# AteGates.net
KiCad netlist of a schematic drawn in EAGLE
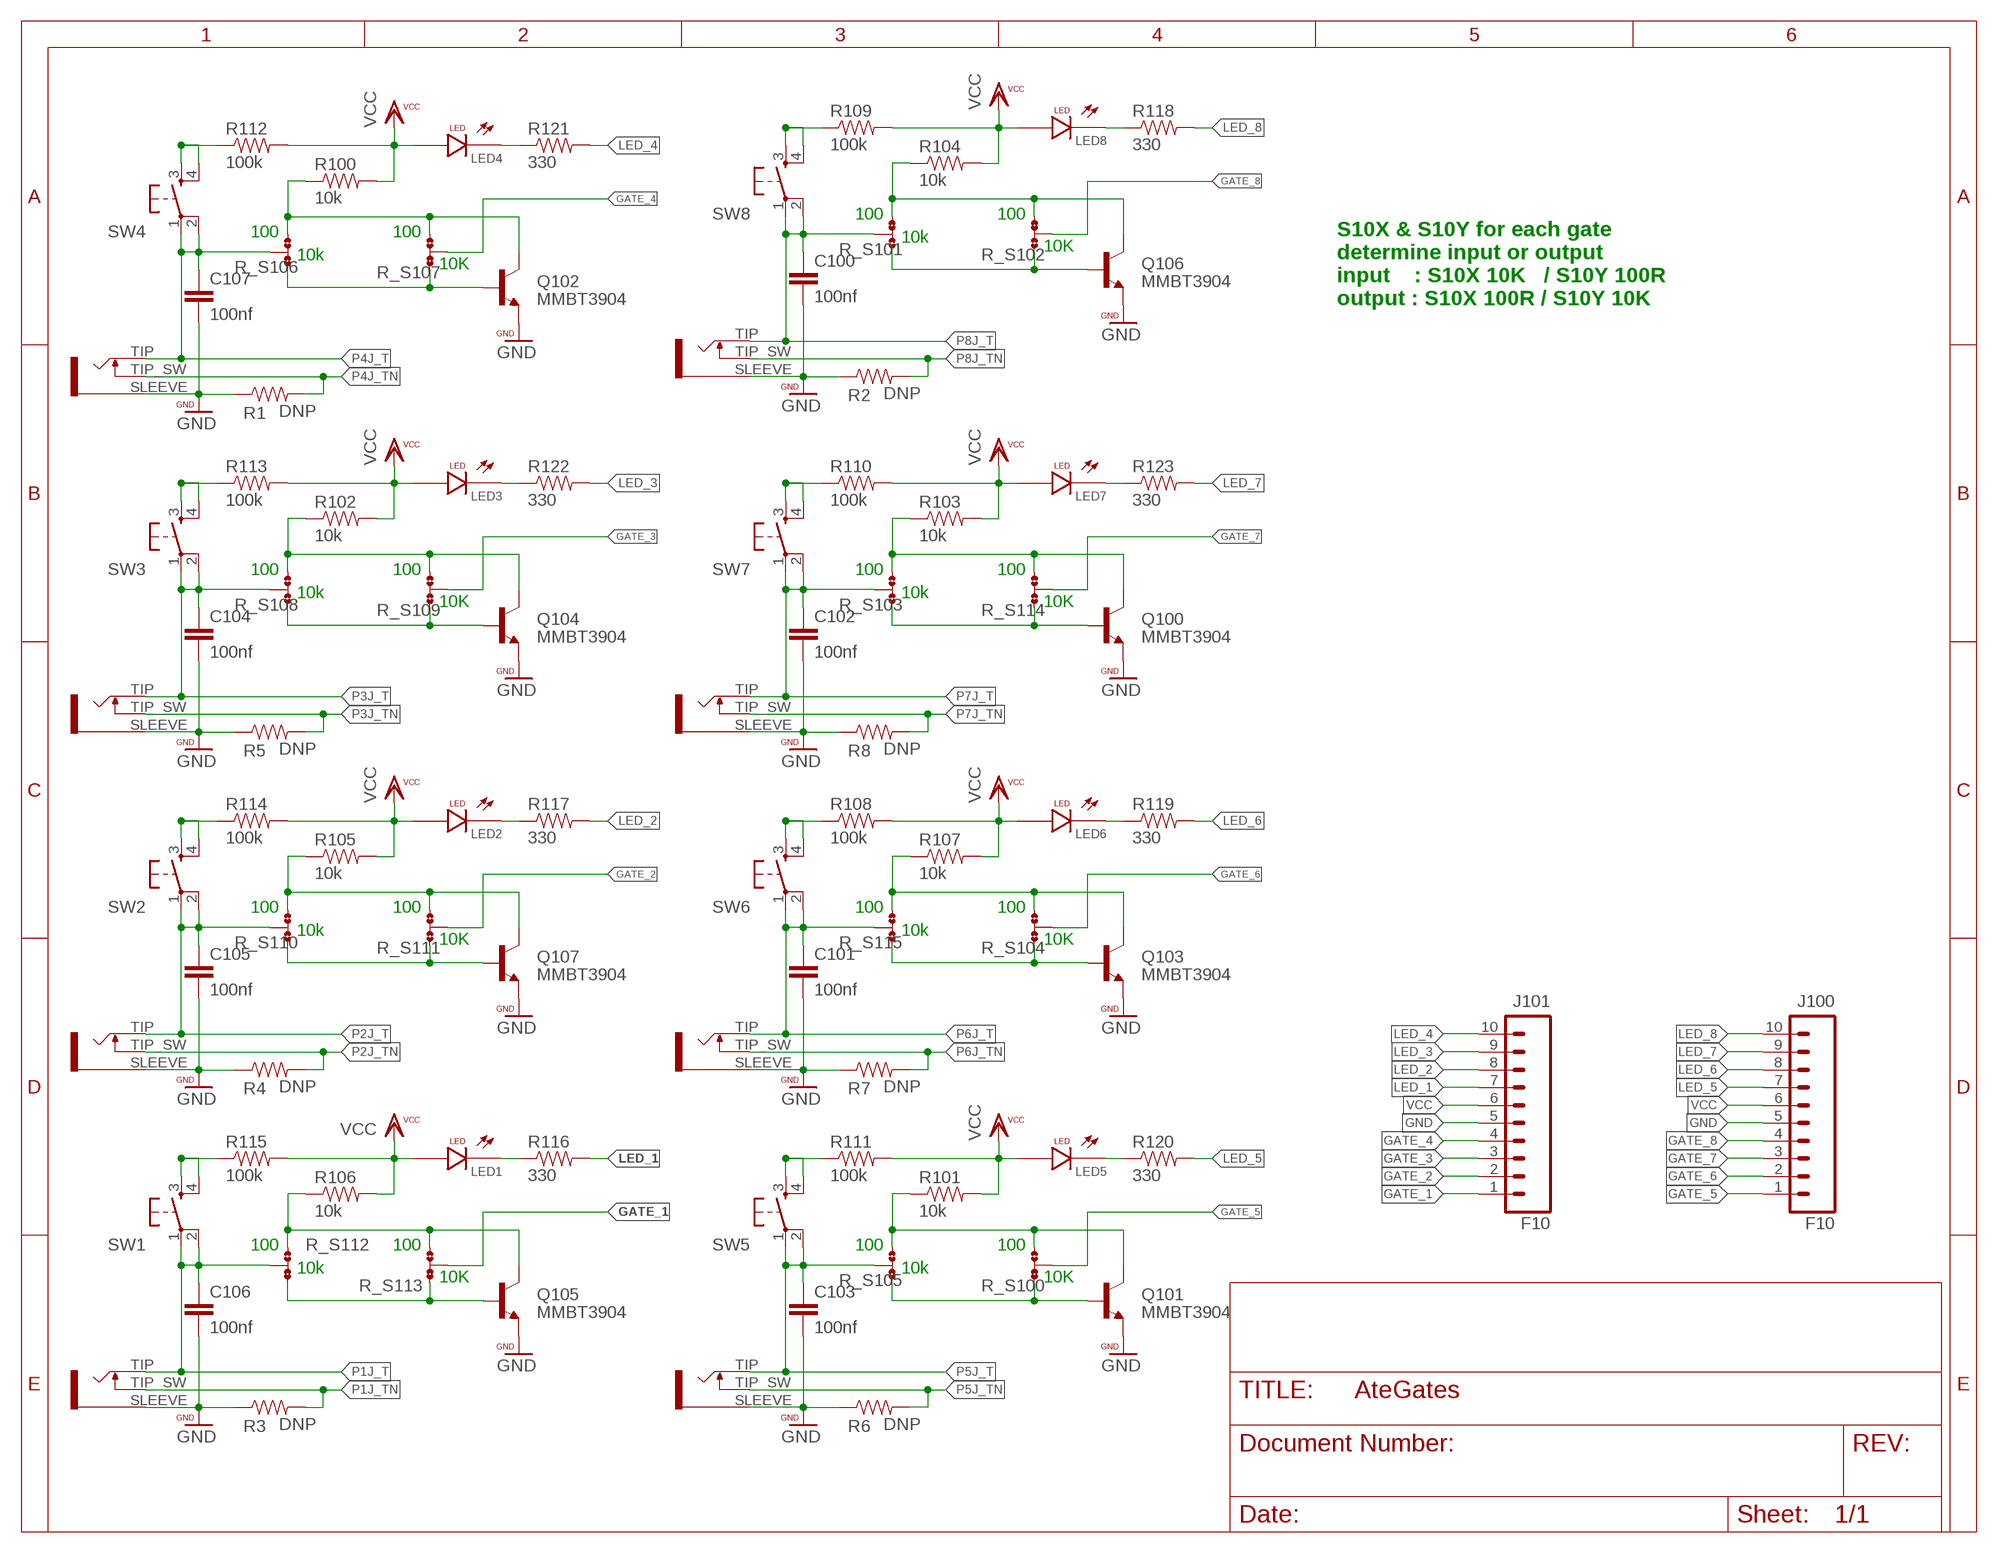
[diagram p0: schematic, sheet 1]

(export (version "E")
  (design (tool "Eeschema 10.0.6"))
  (components
    (comp (ref "C100")
      (value "100nf")
      (footprint "eagle-import:0603-CAP")
      (libsource (lib "eagle-import") (part "CAP0603-CAP"))
    )
    (comp (ref "C101")
      (value "100nf")
      (footprint "eagle-import:0603-CAP")
      (libsource (lib "eagle-import") (part "CAP0603-CAP"))
    )
    (comp (ref "C102")
      (value "100nf")
      (footprint "eagle-import:0603-CAP")
      (libsource (lib "eagle-import") (part "CAP0603-CAP"))
    )
    (comp (ref "C103")
      (value "100nf")
      (footprint "eagle-import:0603-CAP")
      (libsource (lib "eagle-import") (part "CAP0603-CAP"))
    )
    (comp (ref "C104")
      (value "100nf")
      (footprint "eagle-import:0603-CAP")
      (libsource (lib "eagle-import") (part "CAP0603-CAP"))
    )
    (comp (ref "C105")
      (value "100nf")
      (footprint "eagle-import:0603-CAP")
      (libsource (lib "eagle-import") (part "CAP0603-CAP"))
    )
    (comp (ref "C106")
      (value "100nf")
      (footprint "eagle-import:0603-CAP")
      (libsource (lib "eagle-import") (part "CAP0603-CAP"))
    )
    (comp (ref "C107")
      (value "100nf")
      (footprint "eagle-import:0603-CAP")
      (libsource (lib "eagle-import") (part "CAP0603-CAP"))
    )
    (comp (ref "J100")
      (value "F10")
      (footprint "eagle-import:1X10_OCTO")
      (libsource (lib "eagle-import") (part "M10SILK_FEMALE_PTH"))
    )
    (comp (ref "J101")
      (value "F10")
      (footprint "eagle-import:1X10_OCTO")
      (libsource (lib "eagle-import") (part "M10SILK_FEMALE_PTH"))
    )
    (comp (ref "LED1")
      (value "LED")
      (footprint "eagle-import:LED3MM")
      (libsource (lib "eagle-import") (part "LED"))
    )
    (comp (ref "LED2")
      (value "LED")
      (footprint "eagle-import:LED3MM")
      (libsource (lib "eagle-import") (part "LED"))
    )
    (comp (ref "LED3")
      (value "LED")
      (footprint "eagle-import:LED3MM")
      (libsource (lib "eagle-import") (part "LED"))
    )
    (comp (ref "LED4")
      (value "LED")
      (footprint "eagle-import:LED3MM")
      (libsource (lib "eagle-import") (part "LED"))
    )
    (comp (ref "LED5")
      (value "LED")
      (footprint "eagle-import:LED3MM")
      (libsource (lib "eagle-import") (part "LED"))
    )
    (comp (ref "LED6")
      (value "LED")
      (footprint "eagle-import:LED3MM")
      (libsource (lib "eagle-import") (part "LED"))
    )
    (comp (ref "LED7")
      (value "LED")
      (footprint "eagle-import:LED3MM")
      (libsource (lib "eagle-import") (part "LED"))
    )
    (comp (ref "LED8")
      (value "LED")
      (footprint "eagle-import:LED3MM")
      (libsource (lib "eagle-import") (part "LED"))
    )
    (comp (ref "P1J")
      (value "JACK-3_5MM-MONO-SW-WQP_PJ302-12")
      (footprint "eagle-import:WQP_PJ301M-12")
      (libsource (lib "eagle-import") (part "JACK-3_5MM-MONO-SW-WQP_PJ302-12"))
    )
    (comp (ref "P2J")
      (value "JACK-3_5MM-MONO-SW-WQP_PJ302-12")
      (footprint "eagle-import:WQP_PJ301M-12")
      (libsource (lib "eagle-import") (part "JACK-3_5MM-MONO-SW-WQP_PJ302-12"))
    )
    (comp (ref "P3J")
      (value "JACK-3_5MM-MONO-SW-WQP_PJ302-12")
      (footprint "eagle-import:WQP_PJ301M-12")
      (libsource (lib "eagle-import") (part "JACK-3_5MM-MONO-SW-WQP_PJ302-12"))
    )
    (comp (ref "P4J")
      (value "JACK-3_5MM-MONO-SW-WQP_PJ302-12")
      (footprint "eagle-import:WQP_PJ301M-12")
      (libsource (lib "eagle-import") (part "JACK-3_5MM-MONO-SW-WQP_PJ302-12"))
    )
    (comp (ref "P5J")
      (value "JACK-3_5MM-MONO-SW-WQP_PJ302-12")
      (footprint "eagle-import:WQP_PJ301M-12")
      (libsource (lib "eagle-import") (part "JACK-3_5MM-MONO-SW-WQP_PJ302-12"))
    )
    (comp (ref "P6J")
      (value "JACK-3_5MM-MONO-SW-WQP_PJ302-12")
      (footprint "eagle-import:WQP_PJ301M-12")
      (libsource (lib "eagle-import") (part "JACK-3_5MM-MONO-SW-WQP_PJ302-12"))
    )
    (comp (ref "P7J")
      (value "JACK-3_5MM-MONO-SW-WQP_PJ302-12")
      (footprint "eagle-import:WQP_PJ301M-12")
      (libsource (lib "eagle-import") (part "JACK-3_5MM-MONO-SW-WQP_PJ302-12"))
    )
    (comp (ref "P8J")
      (value "JACK-3_5MM-MONO-SW-WQP_PJ302-12")
      (footprint "eagle-import:WQP_PJ301M-12")
      (libsource (lib "eagle-import") (part "JACK-3_5MM-MONO-SW-WQP_PJ302-12"))
    )
    (comp (ref "Q100")
      (value "MMBT3904")
      (footprint "eagle-import:SOT23-BEC")
      (libsource (lib "eagle-import") (part "-NPN-SOT23-BECMMBT3904LT1"))
    )
    (comp (ref "Q101")
      (value "MMBT3904")
      (footprint "eagle-import:SOT23-BEC")
      (libsource (lib "eagle-import") (part "-NPN-SOT23-BECMMBT3904LT1"))
    )
    (comp (ref "Q102")
      (value "MMBT3904")
      (footprint "eagle-import:SOT23-BEC")
      (libsource (lib "eagle-import") (part "-NPN-SOT23-BECMMBT3904LT1"))
    )
    (comp (ref "Q103")
      (value "MMBT3904")
      (footprint "eagle-import:SOT23-BEC")
      (libsource (lib "eagle-import") (part "-NPN-SOT23-BECMMBT3904LT1"))
    )
    (comp (ref "Q104")
      (value "MMBT3904")
      (footprint "eagle-import:SOT23-BEC")
      (libsource (lib "eagle-import") (part "-NPN-SOT23-BECMMBT3904LT1"))
    )
    (comp (ref "Q105")
      (value "MMBT3904")
      (footprint "eagle-import:SOT23-BEC")
      (libsource (lib "eagle-import") (part "-NPN-SOT23-BECMMBT3904LT1"))
    )
    (comp (ref "Q106")
      (value "MMBT3904")
      (footprint "eagle-import:SOT23-BEC")
      (libsource (lib "eagle-import") (part "-NPN-SOT23-BECMMBT3904LT1"))
    )
    (comp (ref "Q107")
      (value "MMBT3904")
      (footprint "eagle-import:SOT23-BEC")
      (libsource (lib "eagle-import") (part "-NPN-SOT23-BECMMBT3904LT1"))
    )
    (comp (ref "R1")
      (value "DNP")
      (footprint "eagle-import:0603-RES")
      (libsource (lib "eagle-import") (part "RESISTOR0603-RES"))
    )
    (comp (ref "R2")
      (value "DNP")
      (footprint "eagle-import:0603-RES")
      (libsource (lib "eagle-import") (part "RESISTOR0603-RES"))
    )
    (comp (ref "R3")
      (value "DNP")
      (footprint "eagle-import:0603-RES")
      (libsource (lib "eagle-import") (part "RESISTOR0603-RES"))
    )
    (comp (ref "R4")
      (value "DNP")
      (footprint "eagle-import:0603-RES")
      (libsource (lib "eagle-import") (part "RESISTOR0603-RES"))
    )
    (comp (ref "R5")
      (value "DNP")
      (footprint "eagle-import:0603-RES")
      (libsource (lib "eagle-import") (part "RESISTOR0603-RES"))
    )
    (comp (ref "R6")
      (value "DNP")
      (footprint "eagle-import:0603-RES")
      (libsource (lib "eagle-import") (part "RESISTOR0603-RES"))
    )
    (comp (ref "R7")
      (value "DNP")
      (footprint "eagle-import:0603-RES")
      (libsource (lib "eagle-import") (part "RESISTOR0603-RES"))
    )
    (comp (ref "R8")
      (value "DNP")
      (footprint "eagle-import:0603-RES")
      (libsource (lib "eagle-import") (part "RESISTOR0603-RES"))
    )
    (comp (ref "R100")
      (value "10k")
      (footprint "eagle-import:0603-RES")
      (libsource (lib "eagle-import") (part "RESISTOR0603-RES"))
    )
    (comp (ref "R101")
      (value "10k")
      (footprint "eagle-import:0603-RES")
      (libsource (lib "eagle-import") (part "RESISTOR0603-RES"))
    )
    (comp (ref "R102")
      (value "10k")
      (footprint "eagle-import:0603-RES")
      (libsource (lib "eagle-import") (part "RESISTOR0603-RES"))
    )
    (comp (ref "R103")
      (value "10k")
      (footprint "eagle-import:0603-RES")
      (libsource (lib "eagle-import") (part "RESISTOR0603-RES"))
    )
    (comp (ref "R104")
      (value "10k")
      (footprint "eagle-import:0603-RES")
      (libsource (lib "eagle-import") (part "RESISTOR0603-RES"))
    )
    (comp (ref "R105")
      (value "10k")
      (footprint "eagle-import:0603-RES")
      (libsource (lib "eagle-import") (part "RESISTOR0603-RES"))
    )
    (comp (ref "R106")
      (value "10k")
      (footprint "eagle-import:0603-RES")
      (libsource (lib "eagle-import") (part "RESISTOR0603-RES"))
    )
    (comp (ref "R107")
      (value "10k")
      (footprint "eagle-import:0603-RES")
      (libsource (lib "eagle-import") (part "RESISTOR0603-RES"))
    )
    (comp (ref "R108")
      (value "100k")
      (footprint "eagle-import:0603-RES")
      (libsource (lib "eagle-import") (part "RESISTOR0603-RES"))
    )
    (comp (ref "R109")
      (value "100k")
      (footprint "eagle-import:0603-RES")
      (libsource (lib "eagle-import") (part "RESISTOR0603-RES"))
    )
    (comp (ref "R110")
      (value "100k")
      (footprint "eagle-import:0603-RES")
      (libsource (lib "eagle-import") (part "RESISTOR0603-RES"))
    )
    (comp (ref "R111")
      (value "100k")
      (footprint "eagle-import:0603-RES")
      (libsource (lib "eagle-import") (part "RESISTOR0603-RES"))
    )
    (comp (ref "R112")
      (value "100k")
      (footprint "eagle-import:0603-RES")
      (libsource (lib "eagle-import") (part "RESISTOR0603-RES"))
    )
    (comp (ref "R113")
      (value "100k")
      (footprint "eagle-import:0603-RES")
      (libsource (lib "eagle-import") (part "RESISTOR0603-RES"))
    )
    (comp (ref "R114")
      (value "100k")
      (footprint "eagle-import:0603-RES")
      (libsource (lib "eagle-import") (part "RESISTOR0603-RES"))
    )
    (comp (ref "R115")
      (value "100k")
      (footprint "eagle-import:0603-RES")
      (libsource (lib "eagle-import") (part "RESISTOR0603-RES"))
    )
    (comp (ref "R116")
      (value "330")
      (footprint "eagle-import:0603-RES")
      (libsource (lib "eagle-import") (part "RESISTOR0603-RES"))
    )
    (comp (ref "R117")
      (value "330")
      (footprint "eagle-import:0603-RES")
      (libsource (lib "eagle-import") (part "RESISTOR0603-RES"))
    )
    (comp (ref "R118")
      (value "330")
      (footprint "eagle-import:0603-RES")
      (libsource (lib "eagle-import") (part "RESISTOR0603-RES"))
    )
    (comp (ref "R119")
      (value "330")
      (footprint "eagle-import:0603-RES")
      (libsource (lib "eagle-import") (part "RESISTOR0603-RES"))
    )
    (comp (ref "R120")
      (value "330")
      (footprint "eagle-import:0603-RES")
      (libsource (lib "eagle-import") (part "RESISTOR0603-RES"))
    )
    (comp (ref "R121")
      (value "330")
      (footprint "eagle-import:0603-RES")
      (libsource (lib "eagle-import") (part "RESISTOR0603-RES"))
    )
    (comp (ref "R122")
      (value "330")
      (footprint "eagle-import:0603-RES")
      (libsource (lib "eagle-import") (part "RESISTOR0603-RES"))
    )
    (comp (ref "R123")
      (value "330")
      (footprint "eagle-import:0603-RES")
      (libsource (lib "eagle-import") (part "RESISTOR0603-RES"))
    )
    (comp (ref "R_S100")
      (value "JMP-3-NO-0603")
      (footprint "eagle-import:JMP-3-NO-0603")
      (libsource (lib "eagle-import") (part "JMP-3-NO-0603"))
    )
    (comp (ref "R_S101")
      (value "100")
      (footprint "eagle-import:JMP-3-NO-0603")
      (libsource (lib "eagle-import") (part "JMP-3-NO-0603"))
    )
    (comp (ref "R_S102")
      (value "JMP-3-NO-0603")
      (footprint "eagle-import:JMP-3-NO-0603")
      (libsource (lib "eagle-import") (part "JMP-3-NO-0603"))
    )
    (comp (ref "R_S103")
      (value "100")
      (footprint "eagle-import:JMP-3-NO-0603")
      (libsource (lib "eagle-import") (part "JMP-3-NO-0603"))
    )
    (comp (ref "R_S104")
      (value "JMP-3-NO-0603")
      (footprint "eagle-import:JMP-3-NO-0603")
      (libsource (lib "eagle-import") (part "JMP-3-NO-0603"))
    )
    (comp (ref "R_S105")
      (value "100")
      (footprint "eagle-import:JMP-3-NO-0603")
      (libsource (lib "eagle-import") (part "JMP-3-NO-0603"))
    )
    (comp (ref "R_S106")
      (value "100")
      (footprint "eagle-import:JMP-3-NO-0603")
      (libsource (lib "eagle-import") (part "JMP-3-NO-0603"))
    )
    (comp (ref "R_S107")
      (value "JMP-3-NO-0603")
      (footprint "eagle-import:JMP-3-NO-0603")
      (libsource (lib "eagle-import") (part "JMP-3-NO-0603"))
    )
    (comp (ref "R_S108")
      (value "100")
      (footprint "eagle-import:JMP-3-NO-0603")
      (libsource (lib "eagle-import") (part "JMP-3-NO-0603"))
    )
    (comp (ref "R_S109")
      (value "JMP-3-NO-0603")
      (footprint "eagle-import:JMP-3-NO-0603")
      (libsource (lib "eagle-import") (part "JMP-3-NO-0603"))
    )
    (comp (ref "R_S110")
      (value "100")
      (footprint "eagle-import:JMP-3-NO-0603")
      (libsource (lib "eagle-import") (part "JMP-3-NO-0603"))
    )
    (comp (ref "R_S111")
      (value "JMP-3-NO-0603")
      (footprint "eagle-import:JMP-3-NO-0603")
      (libsource (lib "eagle-import") (part "JMP-3-NO-0603"))
    )
    (comp (ref "R_S112")
      (value "100")
      (footprint "eagle-import:JMP-3-NO-0603")
      (libsource (lib "eagle-import") (part "JMP-3-NO-0603"))
    )
    (comp (ref "R_S113")
      (value "JMP-3-NO-0603")
      (footprint "eagle-import:JMP-3-NO-0603")
      (libsource (lib "eagle-import") (part "JMP-3-NO-0603"))
    )
    (comp (ref "R_S114")
      (value "JMP-3-NO-0603")
      (footprint "eagle-import:JMP-3-NO-0603")
      (libsource (lib "eagle-import") (part "JMP-3-NO-0603"))
    )
    (comp (ref "R_S115")
      (value "100")
      (footprint "eagle-import:JMP-3-NO-0603")
      (libsource (lib "eagle-import") (part "JMP-3-NO-0603"))
    )
    (comp (ref "SW1")
      (value "TAC_SWITCHPTH")
      (footprint "eagle-import:TACTILE-PTH")
      (libsource (lib "eagle-import") (part "TAC_SWITCHPTH"))
    )
    (comp (ref "SW2")
      (value "TAC_SWITCHPTH")
      (footprint "eagle-import:TACTILE-PTH")
      (libsource (lib "eagle-import") (part "TAC_SWITCHPTH"))
    )
    (comp (ref "SW3")
      (value "TAC_SWITCHPTH")
      (footprint "eagle-import:TACTILE-PTH")
      (libsource (lib "eagle-import") (part "TAC_SWITCHPTH"))
    )
    (comp (ref "SW4")
      (value "TAC_SWITCHPTH")
      (footprint "eagle-import:TACTILE-PTH")
      (libsource (lib "eagle-import") (part "TAC_SWITCHPTH"))
    )
    (comp (ref "SW5")
      (value "TAC_SWITCHPTH")
      (footprint "eagle-import:TACTILE-PTH")
      (libsource (lib "eagle-import") (part "TAC_SWITCHPTH"))
    )
    (comp (ref "SW6")
      (value "TAC_SWITCHPTH")
      (footprint "eagle-import:TACTILE-PTH")
      (libsource (lib "eagle-import") (part "TAC_SWITCHPTH"))
    )
    (comp (ref "SW7")
      (value "TAC_SWITCHPTH")
      (footprint "eagle-import:TACTILE-PTH")
      (libsource (lib "eagle-import") (part "TAC_SWITCHPTH"))
    )
    (comp (ref "SW8")
      (value "TAC_SWITCHPTH")
      (footprint "eagle-import:TACTILE-PTH")
      (libsource (lib "eagle-import") (part "TAC_SWITCHPTH"))
    )
  )
  (nets
    (net (code "1") (name "GATE_1") (class "Default")
      (node (ref "J101") (pin "1") (pinfunction "1_1") (pintype "passive"))
      (node (ref "R_S113") (pin "2") (pinfunction "2_2") (pintype "passive"))
    )
    (net (code "2") (name "GATE_2") (class "Default")
      (node (ref "J101") (pin "2") (pinfunction "2_2") (pintype "passive"))
      (node (ref "R_S111") (pin "2") (pinfunction "2_2") (pintype "passive"))
    )
    (net (code "3") (name "GATE_3") (class "Default")
      (node (ref "J101") (pin "3") (pinfunction "3_3") (pintype "passive"))
      (node (ref "R_S109") (pin "2") (pinfunction "2_2") (pintype "passive"))
    )
    (net (code "4") (name "GATE_4") (class "Default")
      (node (ref "J101") (pin "4") (pinfunction "4_4") (pintype "passive"))
      (node (ref "R_S107") (pin "2") (pinfunction "2_2") (pintype "passive"))
    )
    (net (code "5") (name "GATE_5") (class "Default")
      (node (ref "J100") (pin "1") (pinfunction "1_1") (pintype "passive"))
      (node (ref "R_S100") (pin "2") (pinfunction "2_2") (pintype "passive"))
    )
    (net (code "6") (name "GATE_6") (class "Default")
      (node (ref "J100") (pin "2") (pinfunction "2_2") (pintype "passive"))
      (node (ref "R_S104") (pin "2") (pinfunction "2_2") (pintype "passive"))
    )
    (net (code "7") (name "GATE_7") (class "Default")
      (node (ref "J100") (pin "3") (pinfunction "3_3") (pintype "passive"))
      (node (ref "R_S114") (pin "2") (pinfunction "2_2") (pintype "passive"))
    )
    (net (code "8") (name "GATE_8") (class "Default")
      (node (ref "J100") (pin "4") (pinfunction "4_4") (pintype "passive"))
      (node (ref "R_S102") (pin "2") (pinfunction "2_2") (pintype "passive"))
    )
    (net (code "9") (name "GND") (class "Default")
      (node (ref "C100") (pin "2") (pinfunction "2_2") (pintype "passive"))
      (node (ref "C101") (pin "2") (pinfunction "2_2") (pintype "passive"))
      (node (ref "C102") (pin "2") (pinfunction "2_2") (pintype "passive"))
      (node (ref "C103") (pin "2") (pinfunction "2_2") (pintype "passive"))
      (node (ref "C104") (pin "2") (pinfunction "2_2") (pintype "passive"))
      (node (ref "C105") (pin "2") (pinfunction "2_2") (pintype "passive"))
      (node (ref "C106") (pin "2") (pinfunction "2_2") (pintype "passive"))
      (node (ref "C107") (pin "2") (pinfunction "2_2") (pintype "passive"))
      (node (ref "J100") (pin "5") (pinfunction "5_5") (pintype "passive"))
      (node (ref "J101") (pin "5") (pinfunction "5_5") (pintype "passive"))
      (node (ref "P1J") (pin "SLEEVE") (pinfunction "SLEEVE_SLEEVE") (pintype "passive"))
      (node (ref "P2J") (pin "SLEEVE") (pinfunction "SLEEVE_SLEEVE") (pintype "passive"))
      (node (ref "P3J") (pin "SLEEVE") (pinfunction "SLEEVE_SLEEVE") (pintype "passive"))
      (node (ref "P4J") (pin "SLEEVE") (pinfunction "SLEEVE_SLEEVE") (pintype "passive"))
      (node (ref "P5J") (pin "SLEEVE") (pinfunction "SLEEVE_SLEEVE") (pintype "passive"))
      (node (ref "P6J") (pin "SLEEVE") (pinfunction "SLEEVE_SLEEVE") (pintype "passive"))
      (node (ref "P7J") (pin "SLEEVE") (pinfunction "SLEEVE_SLEEVE") (pintype "passive"))
      (node (ref "P8J") (pin "SLEEVE") (pinfunction "SLEEVE_SLEEVE") (pintype "passive"))
      (node (ref "Q100") (pin "E") (pinfunction "E_E") (pintype "passive"))
      (node (ref "Q101") (pin "E") (pinfunction "E_E") (pintype "passive"))
      (node (ref "Q102") (pin "E") (pinfunction "E_E") (pintype "passive"))
      (node (ref "Q103") (pin "E") (pinfunction "E_E") (pintype "passive"))
      (node (ref "Q104") (pin "E") (pinfunction "E_E") (pintype "passive"))
      (node (ref "Q105") (pin "E") (pinfunction "E_E") (pintype "passive"))
      (node (ref "Q106") (pin "E") (pinfunction "E_E") (pintype "passive"))
      (node (ref "Q107") (pin "E") (pinfunction "E_E") (pintype "passive"))
      (node (ref "R1") (pin "1") (pinfunction "1_1") (pintype "passive"))
      (node (ref "R2") (pin "1") (pinfunction "1_1") (pintype "passive"))
      (node (ref "R3") (pin "1") (pinfunction "1_1") (pintype "passive"))
      (node (ref "R4") (pin "1") (pinfunction "1_1") (pintype "passive"))
      (node (ref "R5") (pin "1") (pinfunction "1_1") (pintype "passive"))
      (node (ref "R6") (pin "1") (pinfunction "1_1") (pintype "passive"))
      (node (ref "R7") (pin "1") (pinfunction "1_1") (pintype "passive"))
      (node (ref "R8") (pin "1") (pinfunction "1_1") (pintype "passive"))
    )
    (net (code "10") (name "LED_1") (class "Default")
      (node (ref "J101") (pin "7") (pinfunction "7_7") (pintype "passive"))
      (node (ref "R116") (pin "2") (pinfunction "2_2") (pintype "passive"))
    )
    (net (code "11") (name "LED_2") (class "Default")
      (node (ref "J101") (pin "8") (pinfunction "8_8") (pintype "passive"))
      (node (ref "R117") (pin "2") (pinfunction "2_2") (pintype "passive"))
    )
    (net (code "12") (name "LED_3") (class "Default")
      (node (ref "J101") (pin "9") (pinfunction "9_9") (pintype "passive"))
      (node (ref "R122") (pin "2") (pinfunction "2_2") (pintype "passive"))
    )
    (net (code "13") (name "LED_4") (class "Default")
      (node (ref "J101") (pin "10") (pinfunction "10_10") (pintype "passive"))
      (node (ref "R121") (pin "2") (pinfunction "2_2") (pintype "passive"))
    )
    (net (code "14") (name "LED_5") (class "Default")
      (node (ref "J100") (pin "7") (pinfunction "7_7") (pintype "passive"))
      (node (ref "R120") (pin "2") (pinfunction "2_2") (pintype "passive"))
    )
    (net (code "15") (name "LED_6") (class "Default")
      (node (ref "J100") (pin "8") (pinfunction "8_8") (pintype "passive"))
      (node (ref "R119") (pin "2") (pinfunction "2_2") (pintype "passive"))
    )
    (net (code "16") (name "LED_7") (class "Default")
      (node (ref "J100") (pin "9") (pinfunction "9_9") (pintype "passive"))
      (node (ref "R123") (pin "2") (pinfunction "2_2") (pintype "passive"))
    )
    (net (code "17") (name "LED_8") (class "Default")
      (node (ref "J100") (pin "10") (pinfunction "10_10") (pintype "passive"))
      (node (ref "R118") (pin "2") (pinfunction "2_2") (pintype "passive"))
    )
    (net (code "18") (name "Net-(LED1-CATHODE)") (class "Default")
      (node (ref "LED1") (pin "K") (pinfunction "CATHODE_K") (pintype "bidirectional"))
      (node (ref "R116") (pin "1") (pinfunction "1_1") (pintype "passive"))
    )
    (net (code "19") (name "Net-(LED2-CATHODE)") (class "Default")
      (node (ref "LED2") (pin "K") (pinfunction "CATHODE_K") (pintype "bidirectional"))
      (node (ref "R117") (pin "1") (pinfunction "1_1") (pintype "passive"))
    )
    (net (code "20") (name "Net-(LED3-CATHODE)") (class "Default")
      (node (ref "LED3") (pin "K") (pinfunction "CATHODE_K") (pintype "bidirectional"))
      (node (ref "R122") (pin "1") (pinfunction "1_1") (pintype "passive"))
    )
    (net (code "21") (name "Net-(LED4-CATHODE)") (class "Default")
      (node (ref "LED4") (pin "K") (pinfunction "CATHODE_K") (pintype "bidirectional"))
      (node (ref "R121") (pin "1") (pinfunction "1_1") (pintype "passive"))
    )
    (net (code "22") (name "Net-(LED5-CATHODE)") (class "Default")
      (node (ref "LED5") (pin "K") (pinfunction "CATHODE_K") (pintype "bidirectional"))
      (node (ref "R120") (pin "1") (pinfunction "1_1") (pintype "passive"))
    )
    (net (code "23") (name "Net-(LED6-CATHODE)") (class "Default")
      (node (ref "LED6") (pin "K") (pinfunction "CATHODE_K") (pintype "bidirectional"))
      (node (ref "R119") (pin "1") (pinfunction "1_1") (pintype "passive"))
    )
    (net (code "24") (name "Net-(LED7-CATHODE)") (class "Default")
      (node (ref "LED7") (pin "K") (pinfunction "CATHODE_K") (pintype "bidirectional"))
      (node (ref "R123") (pin "1") (pinfunction "1_1") (pintype "passive"))
    )
    (net (code "25") (name "Net-(LED8-CATHODE)") (class "Default")
      (node (ref "LED8") (pin "K") (pinfunction "CATHODE_K") (pintype "bidirectional"))
      (node (ref "R118") (pin "1") (pinfunction "1_1") (pintype "passive"))
    )
    (net (code "26") (name "Net-(Q100-PadB)") (class "Default")
      (node (ref "Q100") (pin "B") (pinfunction "B_B") (pintype "passive"))
      (node (ref "R_S103") (pin "3") (pinfunction "3_3") (pintype "passive"))
      (node (ref "R_S114") (pin "3") (pinfunction "3_3") (pintype "passive"))
    )
    (net (code "27") (name "Net-(Q100-PadC)") (class "Default")
      (node (ref "Q100") (pin "C") (pinfunction "C_C") (pintype "passive"))
      (node (ref "R103") (pin "1") (pinfunction "1_1") (pintype "passive"))
      (node (ref "R_S103") (pin "1") (pinfunction "1_1") (pintype "passive"))
      (node (ref "R_S114") (pin "1") (pinfunction "1_1") (pintype "passive"))
    )
    (net (code "28") (name "Net-(Q101-PadB)") (class "Default")
      (node (ref "Q101") (pin "B") (pinfunction "B_B") (pintype "passive"))
      (node (ref "R_S100") (pin "3") (pinfunction "3_3") (pintype "passive"))
      (node (ref "R_S105") (pin "3") (pinfunction "3_3") (pintype "passive"))
    )
    (net (code "29") (name "Net-(Q101-PadC)") (class "Default")
      (node (ref "Q101") (pin "C") (pinfunction "C_C") (pintype "passive"))
      (node (ref "R101") (pin "1") (pinfunction "1_1") (pintype "passive"))
      (node (ref "R_S100") (pin "1") (pinfunction "1_1") (pintype "passive"))
      (node (ref "R_S105") (pin "1") (pinfunction "1_1") (pintype "passive"))
    )
    (net (code "30") (name "Net-(Q102-PadB)") (class "Default")
      (node (ref "Q102") (pin "B") (pinfunction "B_B") (pintype "passive"))
      (node (ref "R_S106") (pin "3") (pinfunction "3_3") (pintype "passive"))
      (node (ref "R_S107") (pin "3") (pinfunction "3_3") (pintype "passive"))
    )
    (net (code "31") (name "Net-(Q102-PadC)") (class "Default")
      (node (ref "Q102") (pin "C") (pinfunction "C_C") (pintype "passive"))
      (node (ref "R100") (pin "1") (pinfunction "1_1") (pintype "passive"))
      (node (ref "R_S106") (pin "1") (pinfunction "1_1") (pintype "passive"))
      (node (ref "R_S107") (pin "1") (pinfunction "1_1") (pintype "passive"))
    )
    (net (code "32") (name "Net-(Q103-PadB)") (class "Default")
      (node (ref "Q103") (pin "B") (pinfunction "B_B") (pintype "passive"))
      (node (ref "R_S104") (pin "3") (pinfunction "3_3") (pintype "passive"))
      (node (ref "R_S115") (pin "3") (pinfunction "3_3") (pintype "passive"))
    )
    (net (code "33") (name "Net-(Q103-PadC)") (class "Default")
      (node (ref "Q103") (pin "C") (pinfunction "C_C") (pintype "passive"))
      (node (ref "R107") (pin "1") (pinfunction "1_1") (pintype "passive"))
      (node (ref "R_S104") (pin "1") (pinfunction "1_1") (pintype "passive"))
      (node (ref "R_S115") (pin "1") (pinfunction "1_1") (pintype "passive"))
    )
    (net (code "34") (name "Net-(Q104-PadB)") (class "Default")
      (node (ref "Q104") (pin "B") (pinfunction "B_B") (pintype "passive"))
      (node (ref "R_S108") (pin "3") (pinfunction "3_3") (pintype "passive"))
      (node (ref "R_S109") (pin "3") (pinfunction "3_3") (pintype "passive"))
    )
    (net (code "35") (name "Net-(Q104-PadC)") (class "Default")
      (node (ref "Q104") (pin "C") (pinfunction "C_C") (pintype "passive"))
      (node (ref "R102") (pin "1") (pinfunction "1_1") (pintype "passive"))
      (node (ref "R_S108") (pin "1") (pinfunction "1_1") (pintype "passive"))
      (node (ref "R_S109") (pin "1") (pinfunction "1_1") (pintype "passive"))
    )
    (net (code "36") (name "Net-(Q105-PadB)") (class "Default")
      (node (ref "Q105") (pin "B") (pinfunction "B_B") (pintype "passive"))
      (node (ref "R_S112") (pin "3") (pinfunction "3_3") (pintype "passive"))
      (node (ref "R_S113") (pin "3") (pinfunction "3_3") (pintype "passive"))
    )
    (net (code "37") (name "Net-(Q105-PadC)") (class "Default")
      (node (ref "Q105") (pin "C") (pinfunction "C_C") (pintype "passive"))
      (node (ref "R106") (pin "1") (pinfunction "1_1") (pintype "passive"))
      (node (ref "R_S112") (pin "1") (pinfunction "1_1") (pintype "passive"))
      (node (ref "R_S113") (pin "1") (pinfunction "1_1") (pintype "passive"))
    )
    (net (code "38") (name "Net-(Q106-PadB)") (class "Default")
      (node (ref "Q106") (pin "B") (pinfunction "B_B") (pintype "passive"))
      (node (ref "R_S101") (pin "3") (pinfunction "3_3") (pintype "passive"))
      (node (ref "R_S102") (pin "3") (pinfunction "3_3") (pintype "passive"))
    )
    (net (code "39") (name "Net-(Q106-PadC)") (class "Default")
      (node (ref "Q106") (pin "C") (pinfunction "C_C") (pintype "passive"))
      (node (ref "R104") (pin "1") (pinfunction "1_1") (pintype "passive"))
      (node (ref "R_S101") (pin "1") (pinfunction "1_1") (pintype "passive"))
      (node (ref "R_S102") (pin "1") (pinfunction "1_1") (pintype "passive"))
    )
    (net (code "40") (name "Net-(Q107-PadB)") (class "Default")
      (node (ref "Q107") (pin "B") (pinfunction "B_B") (pintype "passive"))
      (node (ref "R_S110") (pin "3") (pinfunction "3_3") (pintype "passive"))
      (node (ref "R_S111") (pin "3") (pinfunction "3_3") (pintype "passive"))
    )
    (net (code "41") (name "Net-(Q107-PadC)") (class "Default")
      (node (ref "Q107") (pin "C") (pinfunction "C_C") (pintype "passive"))
      (node (ref "R105") (pin "1") (pinfunction "1_1") (pintype "passive"))
      (node (ref "R_S110") (pin "1") (pinfunction "1_1") (pintype "passive"))
      (node (ref "R_S111") (pin "1") (pinfunction "1_1") (pintype "passive"))
    )
    (net (code "42") (name "Net-(R108-Pad1)") (class "Default")
      (node (ref "R108") (pin "1") (pinfunction "1_1") (pintype "passive"))
      (node (ref "SW6") (pin "3") (pinfunction "3_3") (pintype "passive"))
      (node (ref "SW6") (pin "4") (pinfunction "4_4") (pintype "passive"))
    )
    (net (code "43") (name "Net-(R109-Pad1)") (class "Default")
      (node (ref "R109") (pin "1") (pinfunction "1_1") (pintype "passive"))
      (node (ref "SW8") (pin "3") (pinfunction "3_3") (pintype "passive"))
      (node (ref "SW8") (pin "4") (pinfunction "4_4") (pintype "passive"))
    )
    (net (code "44") (name "Net-(R110-Pad1)") (class "Default")
      (node (ref "R110") (pin "1") (pinfunction "1_1") (pintype "passive"))
      (node (ref "SW7") (pin "3") (pinfunction "3_3") (pintype "passive"))
      (node (ref "SW7") (pin "4") (pinfunction "4_4") (pintype "passive"))
    )
    (net (code "45") (name "Net-(R111-Pad1)") (class "Default")
      (node (ref "R111") (pin "1") (pinfunction "1_1") (pintype "passive"))
      (node (ref "SW5") (pin "3") (pinfunction "3_3") (pintype "passive"))
      (node (ref "SW5") (pin "4") (pinfunction "4_4") (pintype "passive"))
    )
    (net (code "46") (name "Net-(R112-Pad1)") (class "Default")
      (node (ref "R112") (pin "1") (pinfunction "1_1") (pintype "passive"))
      (node (ref "SW4") (pin "3") (pinfunction "3_3") (pintype "passive"))
      (node (ref "SW4") (pin "4") (pinfunction "4_4") (pintype "passive"))
    )
    (net (code "47") (name "Net-(R113-Pad1)") (class "Default")
      (node (ref "R113") (pin "1") (pinfunction "1_1") (pintype "passive"))
      (node (ref "SW3") (pin "3") (pinfunction "3_3") (pintype "passive"))
      (node (ref "SW3") (pin "4") (pinfunction "4_4") (pintype "passive"))
    )
    (net (code "48") (name "Net-(R114-Pad1)") (class "Default")
      (node (ref "R114") (pin "1") (pinfunction "1_1") (pintype "passive"))
      (node (ref "SW2") (pin "3") (pinfunction "3_3") (pintype "passive"))
      (node (ref "SW2") (pin "4") (pinfunction "4_4") (pintype "passive"))
    )
    (net (code "49") (name "Net-(R115-Pad1)") (class "Default")
      (node (ref "R115") (pin "1") (pinfunction "1_1") (pintype "passive"))
      (node (ref "SW1") (pin "3") (pinfunction "3_3") (pintype "passive"))
      (node (ref "SW1") (pin "4") (pinfunction "4_4") (pintype "passive"))
    )
    (net (code "50") (name "P1J_T") (class "Default")
      (node (ref "C106") (pin "1") (pinfunction "1_1") (pintype "passive"))
      (node (ref "P1J") (pin "TIP") (pinfunction "TIP_TIP") (pintype "passive"))
      (node (ref "R_S112") (pin "2") (pinfunction "2_2") (pintype "passive"))
      (node (ref "SW1") (pin "1") (pinfunction "1_1") (pintype "passive"))
      (node (ref "SW1") (pin "2") (pinfunction "2_2") (pintype "passive"))
    )
    (net (code "51") (name "P1J_TN") (class "Default")
      (node (ref "P1J") (pin "TIP_SW") (pinfunction "TIP_SW_TIP_SW") (pintype "passive"))
      (node (ref "R3") (pin "2") (pinfunction "2_2") (pintype "passive"))
    )
    (net (code "52") (name "P2J_T") (class "Default")
      (node (ref "C105") (pin "1") (pinfunction "1_1") (pintype "passive"))
      (node (ref "P2J") (pin "TIP") (pinfunction "TIP_TIP") (pintype "passive"))
      (node (ref "R_S110") (pin "2") (pinfunction "2_2") (pintype "passive"))
      (node (ref "SW2") (pin "1") (pinfunction "1_1") (pintype "passive"))
      (node (ref "SW2") (pin "2") (pinfunction "2_2") (pintype "passive"))
    )
    (net (code "53") (name "P2J_TN") (class "Default")
      (node (ref "P2J") (pin "TIP_SW") (pinfunction "TIP_SW_TIP_SW") (pintype "passive"))
      (node (ref "R4") (pin "2") (pinfunction "2_2") (pintype "passive"))
    )
    (net (code "54") (name "P3J_T") (class "Default")
      (node (ref "C104") (pin "1") (pinfunction "1_1") (pintype "passive"))
      (node (ref "P3J") (pin "TIP") (pinfunction "TIP_TIP") (pintype "passive"))
      (node (ref "R_S108") (pin "2") (pinfunction "2_2") (pintype "passive"))
      (node (ref "SW3") (pin "1") (pinfunction "1_1") (pintype "passive"))
      (node (ref "SW3") (pin "2") (pinfunction "2_2") (pintype "passive"))
    )
    (net (code "55") (name "P3J_TN") (class "Default")
      (node (ref "P3J") (pin "TIP_SW") (pinfunction "TIP_SW_TIP_SW") (pintype "passive"))
      (node (ref "R5") (pin "2") (pinfunction "2_2") (pintype "passive"))
    )
    (net (code "56") (name "P4J_T") (class "Default")
      (node (ref "C107") (pin "1") (pinfunction "1_1") (pintype "passive"))
      (node (ref "P4J") (pin "TIP") (pinfunction "TIP_TIP") (pintype "passive"))
      (node (ref "R_S106") (pin "2") (pinfunction "2_2") (pintype "passive"))
      (node (ref "SW4") (pin "1") (pinfunction "1_1") (pintype "passive"))
      (node (ref "SW4") (pin "2") (pinfunction "2_2") (pintype "passive"))
    )
    (net (code "57") (name "P4J_TN") (class "Default")
      (node (ref "P4J") (pin "TIP_SW") (pinfunction "TIP_SW_TIP_SW") (pintype "passive"))
      (node (ref "R1") (pin "2") (pinfunction "2_2") (pintype "passive"))
    )
    (net (code "58") (name "P5J_T") (class "Default")
      (node (ref "C103") (pin "1") (pinfunction "1_1") (pintype "passive"))
      (node (ref "P5J") (pin "TIP") (pinfunction "TIP_TIP") (pintype "passive"))
      (node (ref "R_S105") (pin "2") (pinfunction "2_2") (pintype "passive"))
      (node (ref "SW5") (pin "1") (pinfunction "1_1") (pintype "passive"))
      (node (ref "SW5") (pin "2") (pinfunction "2_2") (pintype "passive"))
    )
    (net (code "59") (name "P5J_TN") (class "Default")
      (node (ref "P5J") (pin "TIP_SW") (pinfunction "TIP_SW_TIP_SW") (pintype "passive"))
      (node (ref "R6") (pin "2") (pinfunction "2_2") (pintype "passive"))
    )
    (net (code "60") (name "P6J_T") (class "Default")
      (node (ref "C101") (pin "1") (pinfunction "1_1") (pintype "passive"))
      (node (ref "P6J") (pin "TIP") (pinfunction "TIP_TIP") (pintype "passive"))
      (node (ref "R_S115") (pin "2") (pinfunction "2_2") (pintype "passive"))
      (node (ref "SW6") (pin "1") (pinfunction "1_1") (pintype "passive"))
      (node (ref "SW6") (pin "2") (pinfunction "2_2") (pintype "passive"))
    )
    (net (code "61") (name "P6J_TN") (class "Default")
      (node (ref "P6J") (pin "TIP_SW") (pinfunction "TIP_SW_TIP_SW") (pintype "passive"))
      (node (ref "R7") (pin "2") (pinfunction "2_2") (pintype "passive"))
    )
    (net (code "62") (name "P7J_T") (class "Default")
      (node (ref "C102") (pin "1") (pinfunction "1_1") (pintype "passive"))
      (node (ref "P7J") (pin "TIP") (pinfunction "TIP_TIP") (pintype "passive"))
      (node (ref "R_S103") (pin "2") (pinfunction "2_2") (pintype "passive"))
      (node (ref "SW7") (pin "1") (pinfunction "1_1") (pintype "passive"))
      (node (ref "SW7") (pin "2") (pinfunction "2_2") (pintype "passive"))
    )
    (net (code "63") (name "P7J_TN") (class "Default")
      (node (ref "P7J") (pin "TIP_SW") (pinfunction "TIP_SW_TIP_SW") (pintype "passive"))
      (node (ref "R8") (pin "2") (pinfunction "2_2") (pintype "passive"))
    )
    (net (code "64") (name "P8J_T") (class "Default")
      (node (ref "C100") (pin "1") (pinfunction "1_1") (pintype "passive"))
      (node (ref "P8J") (pin "TIP") (pinfunction "TIP_TIP") (pintype "passive"))
      (node (ref "R_S101") (pin "2") (pinfunction "2_2") (pintype "passive"))
      (node (ref "SW8") (pin "1") (pinfunction "1_1") (pintype "passive"))
      (node (ref "SW8") (pin "2") (pinfunction "2_2") (pintype "passive"))
    )
    (net (code "65") (name "P8J_TN") (class "Default")
      (node (ref "P8J") (pin "TIP_SW") (pinfunction "TIP_SW_TIP_SW") (pintype "passive"))
      (node (ref "R2") (pin "2") (pinfunction "2_2") (pintype "passive"))
    )
    (net (code "66") (name "VCC") (class "Default")
      (node (ref "J100") (pin "6") (pinfunction "6_6") (pintype "passive"))
      (node (ref "J101") (pin "6") (pinfunction "6_6") (pintype "passive"))
      (node (ref "LED1") (pin "A") (pinfunction "ANODE_A") (pintype "bidirectional"))
      (node (ref "LED2") (pin "A") (pinfunction "ANODE_A") (pintype "bidirectional"))
      (node (ref "LED3") (pin "A") (pinfunction "ANODE_A") (pintype "bidirectional"))
      (node (ref "LED4") (pin "A") (pinfunction "ANODE_A") (pintype "bidirectional"))
      (node (ref "LED5") (pin "A") (pinfunction "ANODE_A") (pintype "bidirectional"))
      (node (ref "LED6") (pin "A") (pinfunction "ANODE_A") (pintype "bidirectional"))
      (node (ref "LED7") (pin "A") (pinfunction "ANODE_A") (pintype "bidirectional"))
      (node (ref "LED8") (pin "A") (pinfunction "ANODE_A") (pintype "bidirectional"))
      (node (ref "R100") (pin "2") (pinfunction "2_2") (pintype "passive"))
      (node (ref "R101") (pin "2") (pinfunction "2_2") (pintype "passive"))
      (node (ref "R102") (pin "2") (pinfunction "2_2") (pintype "passive"))
      (node (ref "R103") (pin "2") (pinfunction "2_2") (pintype "passive"))
      (node (ref "R104") (pin "2") (pinfunction "2_2") (pintype "passive"))
      (node (ref "R105") (pin "2") (pinfunction "2_2") (pintype "passive"))
      (node (ref "R106") (pin "2") (pinfunction "2_2") (pintype "passive"))
      (node (ref "R107") (pin "2") (pinfunction "2_2") (pintype "passive"))
      (node (ref "R108") (pin "2") (pinfunction "2_2") (pintype "passive"))
      (node (ref "R109") (pin "2") (pinfunction "2_2") (pintype "passive"))
      (node (ref "R110") (pin "2") (pinfunction "2_2") (pintype "passive"))
      (node (ref "R111") (pin "2") (pinfunction "2_2") (pintype "passive"))
      (node (ref "R112") (pin "2") (pinfunction "2_2") (pintype "passive"))
      (node (ref "R113") (pin "2") (pinfunction "2_2") (pintype "passive"))
      (node (ref "R114") (pin "2") (pinfunction "2_2") (pintype "passive"))
      (node (ref "R115") (pin "2") (pinfunction "2_2") (pintype "passive"))
    )
  )
)
